# thermocouple.net
KiCad netlist of a schematic drawn in EAGLE
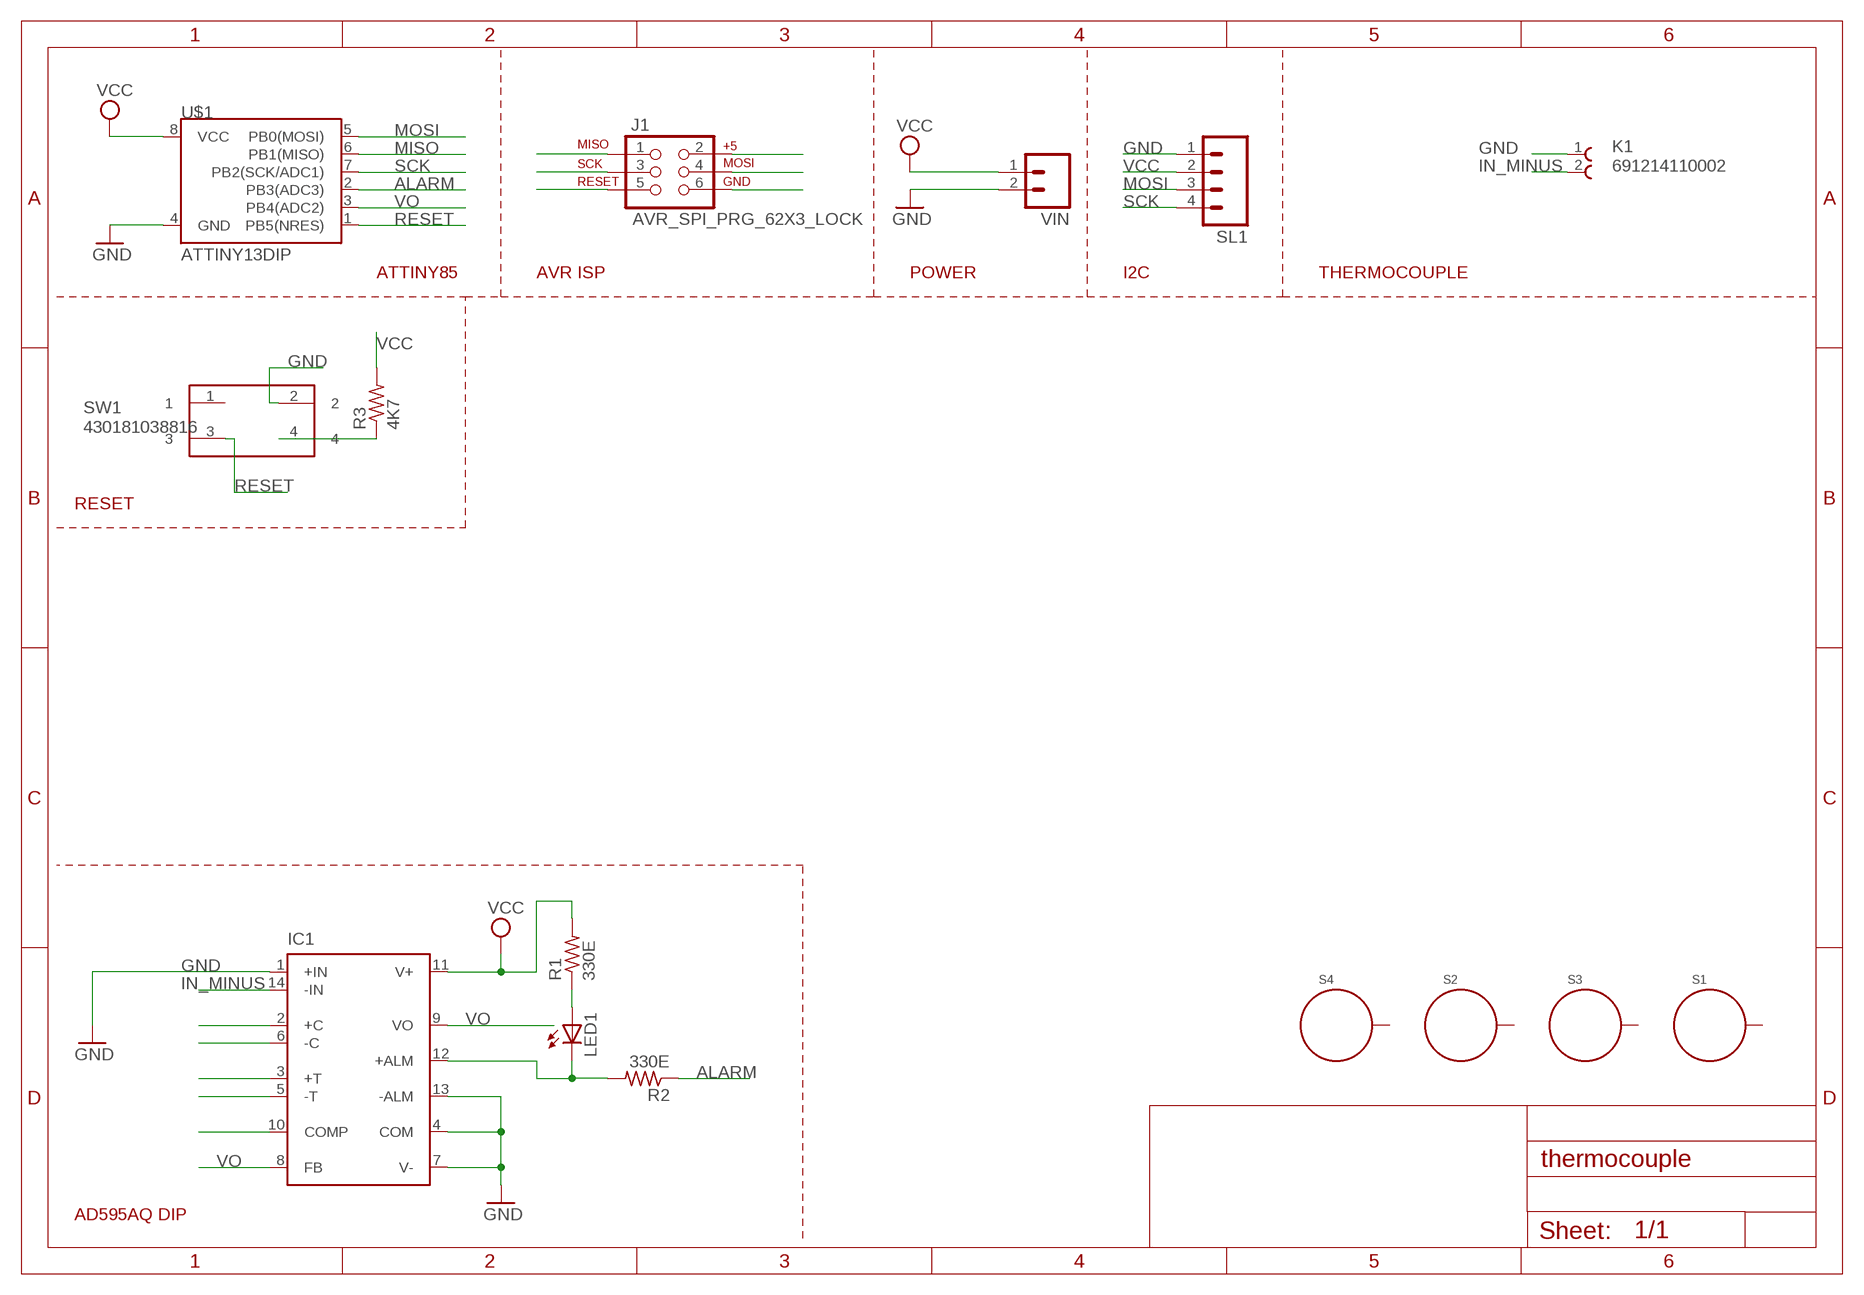
[diagram p0: schematic, sheet 1]

(export (version "E")
  (design (tool "Eeschema 10.0.6"))
  (components
    (comp (ref "IC1")
      (value "AD595")
      (footprint "eagle-import:DIL14")
      (fields (field (name "MPN") "AD595AQ"))
      (libsource (lib "eagle-import") (part "AD595"))
    )
    (comp (ref "J1")
      (value "AVR_SPI_PRG_62X3_LOCK")
      (footprint "eagle-import:2X3_LOCK")
      (libsource (lib "eagle-import") (part "AVR_SPI_PRG_62X3_LOCK"))
    )
    (comp (ref "K1")
      (value "691214110002")
      (footprint "eagle-import:691214110002")
      (libsource (lib "eagle-import") (part "691214110002"))
    )
    (comp (ref "LED1")
      (value "LEDCHIPLED_0805")
      (footprint "eagle-import:CHIPLED_0805")
      (libsource (lib "eagle-import") (part "LEDCHIPLED_0805"))
    )
    (comp (ref "R1")
      (value "330E")
      (footprint "eagle-import:M0805")
      (libsource (lib "eagle-import") (part "R-US_M0805"))
    )
    (comp (ref "R2")
      (value "330E")
      (footprint "eagle-import:M0805")
      (libsource (lib "eagle-import") (part "R-US_M0805"))
    )
    (comp (ref "R3")
      (value "4K7")
      (footprint "eagle-import:M0805")
      (libsource (lib "eagle-import") (part "R-US_M0805"))
    )
    (comp (ref "S1")
      (value "STANDOFF_ELECTRICAL")
      (footprint "eagle-import:STANDOFF-ELECTRICAL")
      (libsource (lib "eagle-import") (part "STANDOFF_ELECTRICAL"))
    )
    (comp (ref "S2")
      (value "STANDOFF_ELECTRICAL")
      (footprint "eagle-import:STANDOFF-ELECTRICAL")
      (libsource (lib "eagle-import") (part "STANDOFF_ELECTRICAL"))
    )
    (comp (ref "S3")
      (value "STANDOFF_ELECTRICAL")
      (footprint "eagle-import:STANDOFF-ELECTRICAL")
      (libsource (lib "eagle-import") (part "STANDOFF_ELECTRICAL"))
    )
    (comp (ref "S4")
      (value "STANDOFF_ELECTRICAL")
      (footprint "eagle-import:STANDOFF-ELECTRICAL")
      (libsource (lib "eagle-import") (part "STANDOFF_ELECTRICAL"))
    )
    (comp (ref "SL1")
      (value "M04")
      (footprint "eagle-import:04P")
      (libsource (lib "eagle-import") (part "M04"))
    )
    (comp (ref "SW1")
      (value "430181038816")
      (footprint "eagle-import:430181038816")
      (libsource (lib "eagle-import") (part "430181038816"))
    )
    (comp (ref "U$1")
      (value "ATTINY13DIP")
      (footprint "eagle-import:DIP08")
      (libsource (lib "eagle-import") (part "ATTINY13DIP"))
    )
    (comp (ref "VIN")
      (value "M02")
      (footprint "eagle-import:02P")
      (libsource (lib "eagle-import") (part "M02"))
    )
  )
  (nets
    (net (code "1") (name "/ALARM") (class "Default")
      (node (ref "R2") (pin "1") (pinfunction "1_1") (pintype "passive"))
      (node (ref "U$1") (pin "2") (pinfunction "PB3(ADC3)_2") (pintype "bidirectional"))
    )
    (net (code "2") (name "/IN_MINUS") (class "Default")
      (node (ref "IC1") (pin "14") (pinfunction "-IN_14") (pintype "input"))
      (node (ref "K1") (pin "2") (pinfunction "2_2") (pintype "passive"))
    )
    (net (code "3") (name "/MISO") (class "Default")
      (node (ref "J1") (pin "1") (pinfunction "1_1") (pintype "passive"))
      (node (ref "U$1") (pin "6") (pinfunction "PB1(MISO)_6") (pintype "bidirectional"))
    )
    (net (code "4") (name "/MOSI") (class "Default")
      (node (ref "J1") (pin "4") (pinfunction "4_4") (pintype "passive"))
      (node (ref "SL1") (pin "3") (pinfunction "3_3") (pintype "passive"))
      (node (ref "U$1") (pin "5") (pinfunction "PB0(MOSI)_5") (pintype "bidirectional"))
    )
    (net (code "5") (name "/RESET") (class "Default")
      (node (ref "J1") (pin "5") (pinfunction "5_5") (pintype "passive"))
      (node (ref "SW1") (pin "3") (pinfunction "3_3") (pintype "bidirectional"))
      (node (ref "U$1") (pin "1") (pinfunction "PB5(NRES)_1") (pintype "bidirectional"))
    )
    (net (code "6") (name "/SCK") (class "Default")
      (node (ref "J1") (pin "3") (pinfunction "3_3") (pintype "passive"))
      (node (ref "SL1") (pin "4") (pinfunction "4_4") (pintype "passive"))
      (node (ref "U$1") (pin "7") (pinfunction "PB2(SCK/ADC1)_7") (pintype "bidirectional"))
    )
    (net (code "7") (name "/VO") (class "Default")
      (node (ref "IC1") (pin "8") (pinfunction "FB_8") (pintype "passive"))
      (node (ref "IC1") (pin "9") (pinfunction "VO_9") (pintype "output"))
      (node (ref "U$1") (pin "3") (pinfunction "PB4(ADC2)_3") (pintype "bidirectional"))
    )
    (net (code "8") (name "GND") (class "Default")
      (node (ref "IC1") (pin "1") (pinfunction "+IN_1") (pintype "input"))
      (node (ref "IC1") (pin "13") (pinfunction "-ALM_13") (pintype "passive"))
      (node (ref "IC1") (pin "4") (pinfunction "COM_4") (pintype "power_in"))
      (node (ref "IC1") (pin "7") (pinfunction "V-_7") (pintype "power_in"))
      (node (ref "J1") (pin "6") (pinfunction "6_6") (pintype "passive"))
      (node (ref "K1") (pin "1") (pinfunction "1_1") (pintype "passive"))
      (node (ref "SL1") (pin "1") (pinfunction "1_1") (pintype "passive"))
      (node (ref "SW1") (pin "2") (pinfunction "2_2") (pintype "bidirectional"))
      (node (ref "U$1") (pin "4") (pinfunction "GND_4") (pintype "bidirectional"))
      (node (ref "VIN") (pin "2") (pinfunction "2_2") (pintype "passive"))
    )
    (net (code "9") (name "Net-(IC1-+ALM)") (class "Default")
      (node (ref "IC1") (pin "12") (pinfunction "+ALM_12") (pintype "passive"))
      (node (ref "LED1") (pin "C") (pinfunction "C_C") (pintype "passive"))
      (node (ref "R2") (pin "2") (pinfunction "2_2") (pintype "passive"))
    )
    (net (code "10") (name "Net-(LED1-PadA)") (class "Default")
      (node (ref "LED1") (pin "A") (pinfunction "A_A") (pintype "passive"))
      (node (ref "R1") (pin "1") (pinfunction "1_1") (pintype "passive"))
    )
    (net (code "11") (name "Net-(R3-Pad1)") (class "Default")
      (node (ref "R3") (pin "1") (pinfunction "1_1") (pintype "passive"))
      (node (ref "SW1") (pin "4") (pinfunction "4_4") (pintype "bidirectional"))
    )
    (net (code "12") (name "VCC") (class "Default")
      (node (ref "IC1") (pin "11") (pinfunction "V+_11") (pintype "power_in"))
      (node (ref "J1") (pin "2") (pinfunction "2_2") (pintype "passive"))
      (node (ref "R1") (pin "2") (pinfunction "2_2") (pintype "passive"))
      (node (ref "R3") (pin "2") (pinfunction "2_2") (pintype "passive"))
      (node (ref "SL1") (pin "2") (pinfunction "2_2") (pintype "passive"))
      (node (ref "U$1") (pin "8") (pinfunction "VCC_8") (pintype "bidirectional"))
      (node (ref "VIN") (pin "1") (pinfunction "1_1") (pintype "passive"))
    )
    (net (code "13") (name "unconnected-(IC1-+C-Pad2)") (class "Default")
      (node (ref "IC1") (pin "2") (pinfunction "+C_2") (pintype "input"))
    )
    (net (code "14") (name "unconnected-(IC1-+T-Pad3)") (class "Default")
      (node (ref "IC1") (pin "3") (pinfunction "+T_3") (pintype "passive"))
    )
    (net (code "15") (name "unconnected-(IC1--C-Pad6)") (class "Default")
      (node (ref "IC1") (pin "6") (pinfunction "-C_6") (pintype "input"))
    )
    (net (code "16") (name "unconnected-(IC1--T-Pad5)") (class "Default")
      (node (ref "IC1") (pin "5") (pinfunction "-T_5") (pintype "passive"))
    )
    (net (code "17") (name "unconnected-(IC1-COMP-Pad10)") (class "Default")
      (node (ref "IC1") (pin "10") (pinfunction "COMP_10") (pintype "passive"))
    )
    (net (code "18") (name "unconnected-(S1-P$1-PadP1)") (class "Default")
      (node (ref "S1") (pin "P1") (pinfunction "P$1_P1") (pintype "bidirectional"))
    )
    (net (code "19") (name "unconnected-(S2-P$1-PadP1)") (class "Default")
      (node (ref "S2") (pin "P1") (pinfunction "P$1_P1") (pintype "bidirectional"))
    )
    (net (code "20") (name "unconnected-(S3-P$1-PadP1)") (class "Default")
      (node (ref "S3") (pin "P1") (pinfunction "P$1_P1") (pintype "bidirectional"))
    )
    (net (code "21") (name "unconnected-(S4-P$1-PadP1)") (class "Default")
      (node (ref "S4") (pin "P1") (pinfunction "P$1_P1") (pintype "bidirectional"))
    )
    (net (code "22") (name "unconnected-(SW1-Pad1)") (class "Default")
      (node (ref "SW1") (pin "1") (pinfunction "1_1") (pintype "bidirectional"))
    )
  )
)
